# usb2cmi.net
KiCad netlist of a schematic drawn in EAGLE
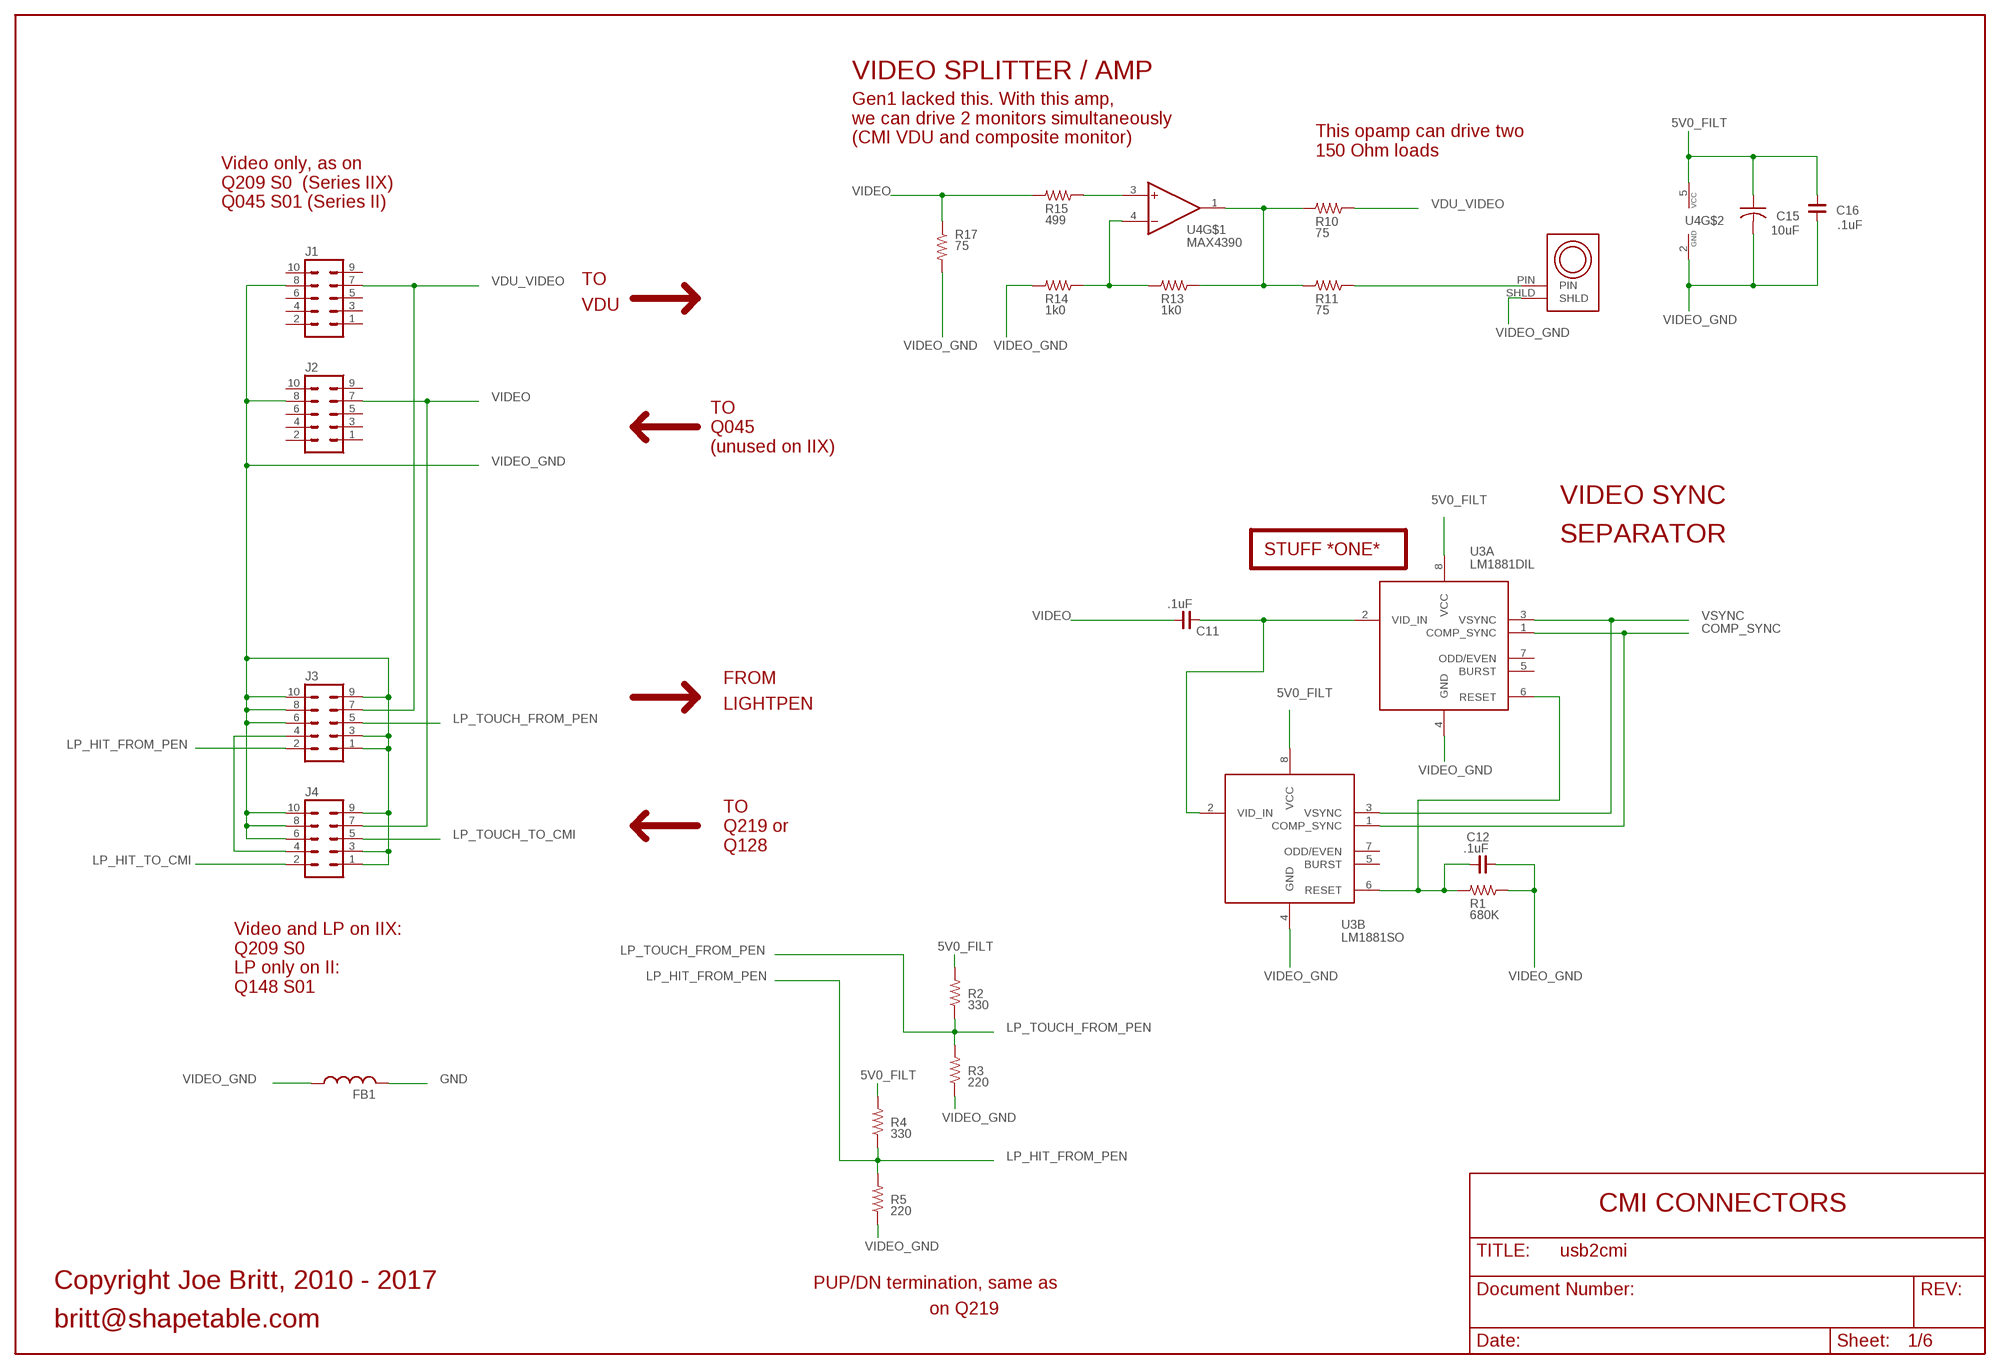
[diagram p0: schematic, sheet 1]
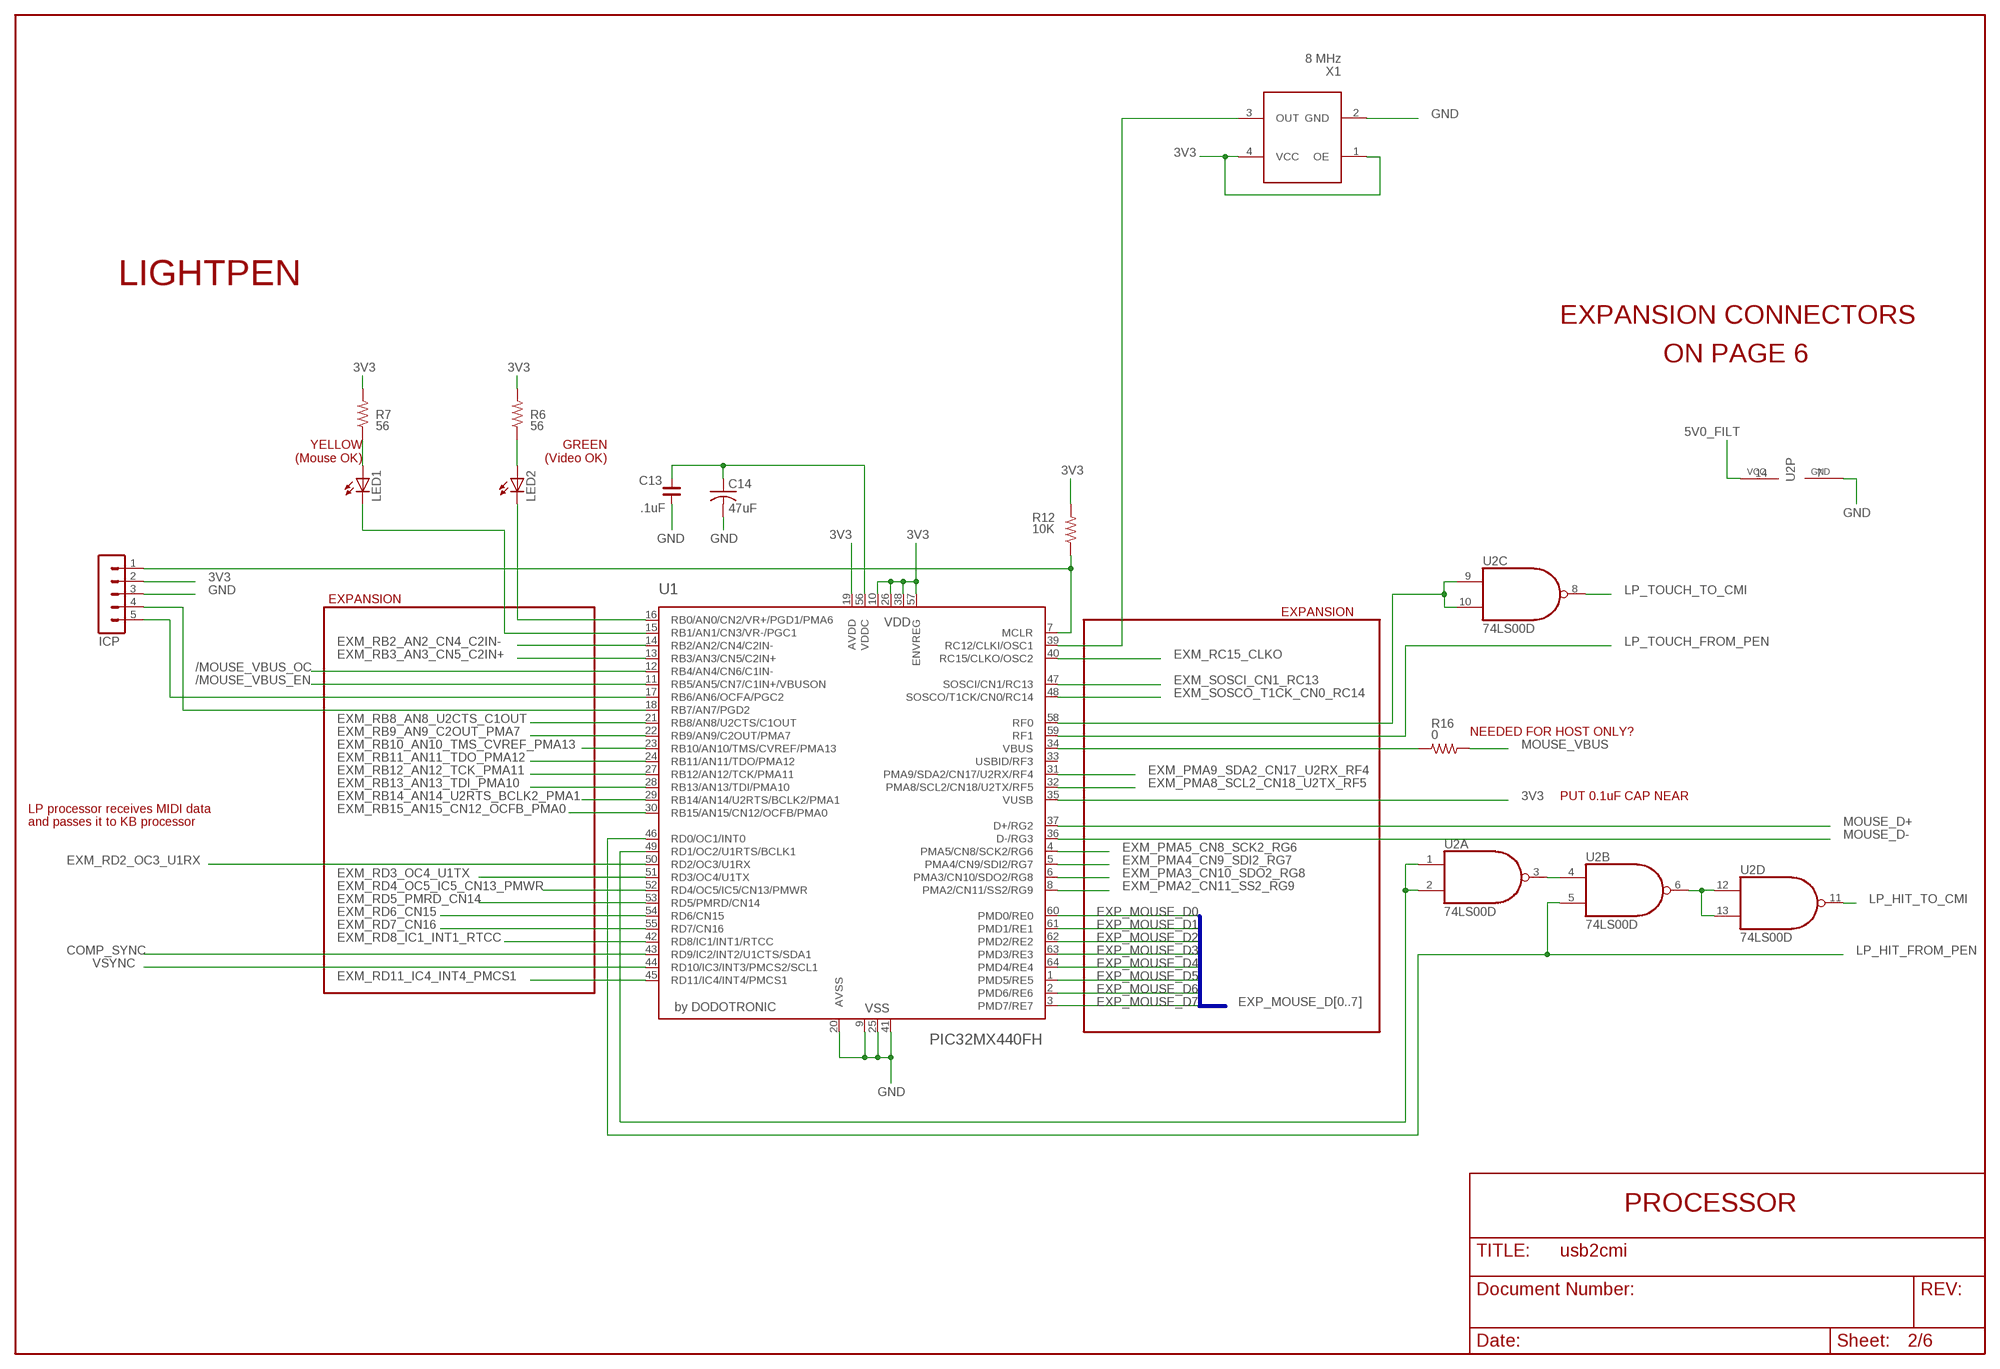
[diagram p1: schematic, sheet 2]
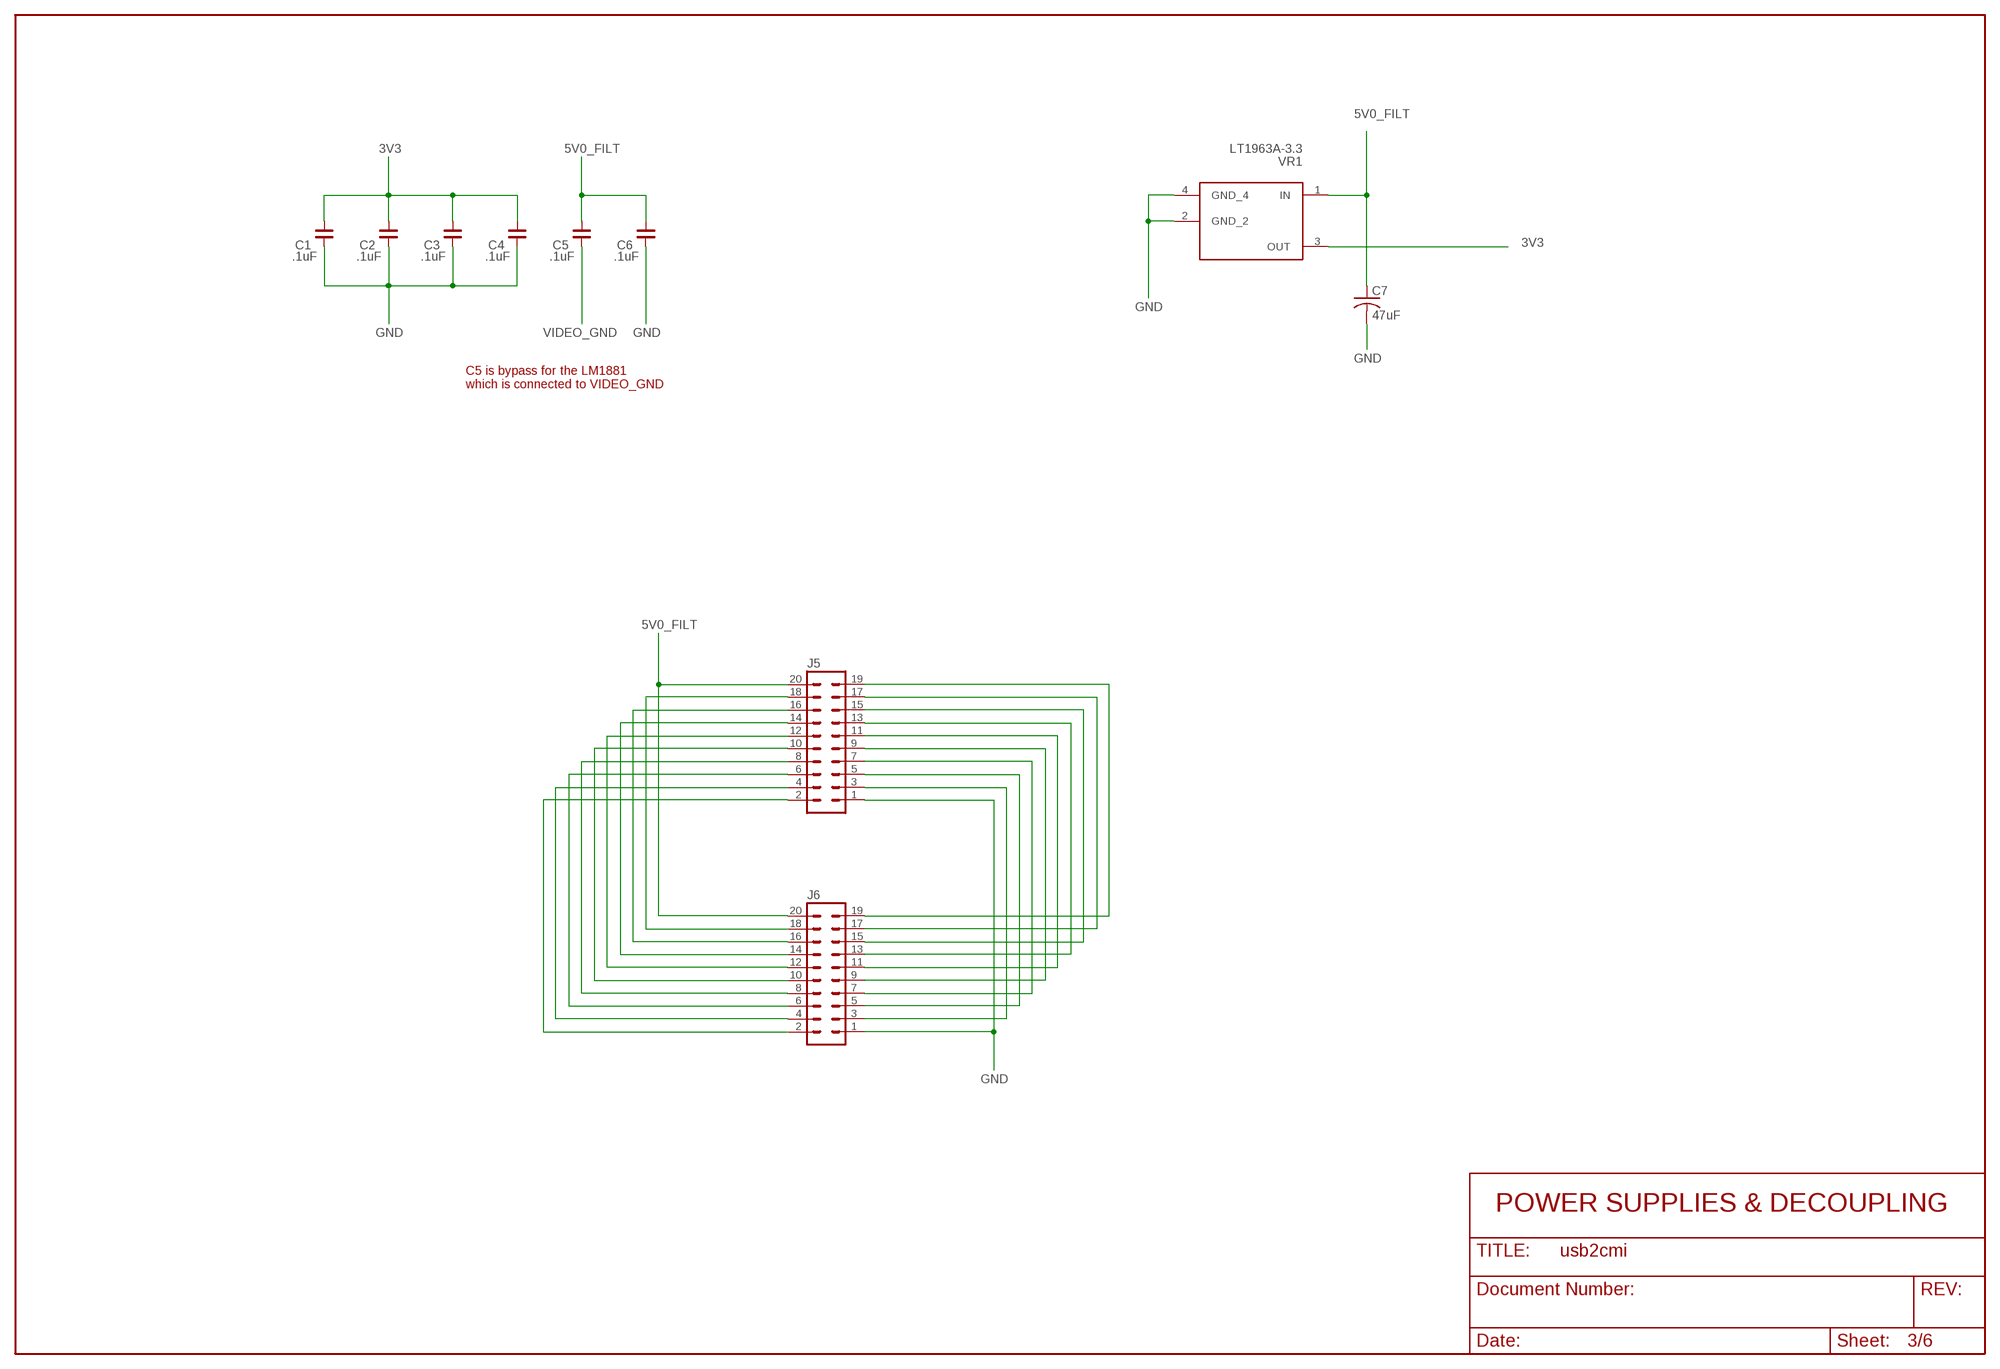
[diagram p2: schematic, sheet 3]
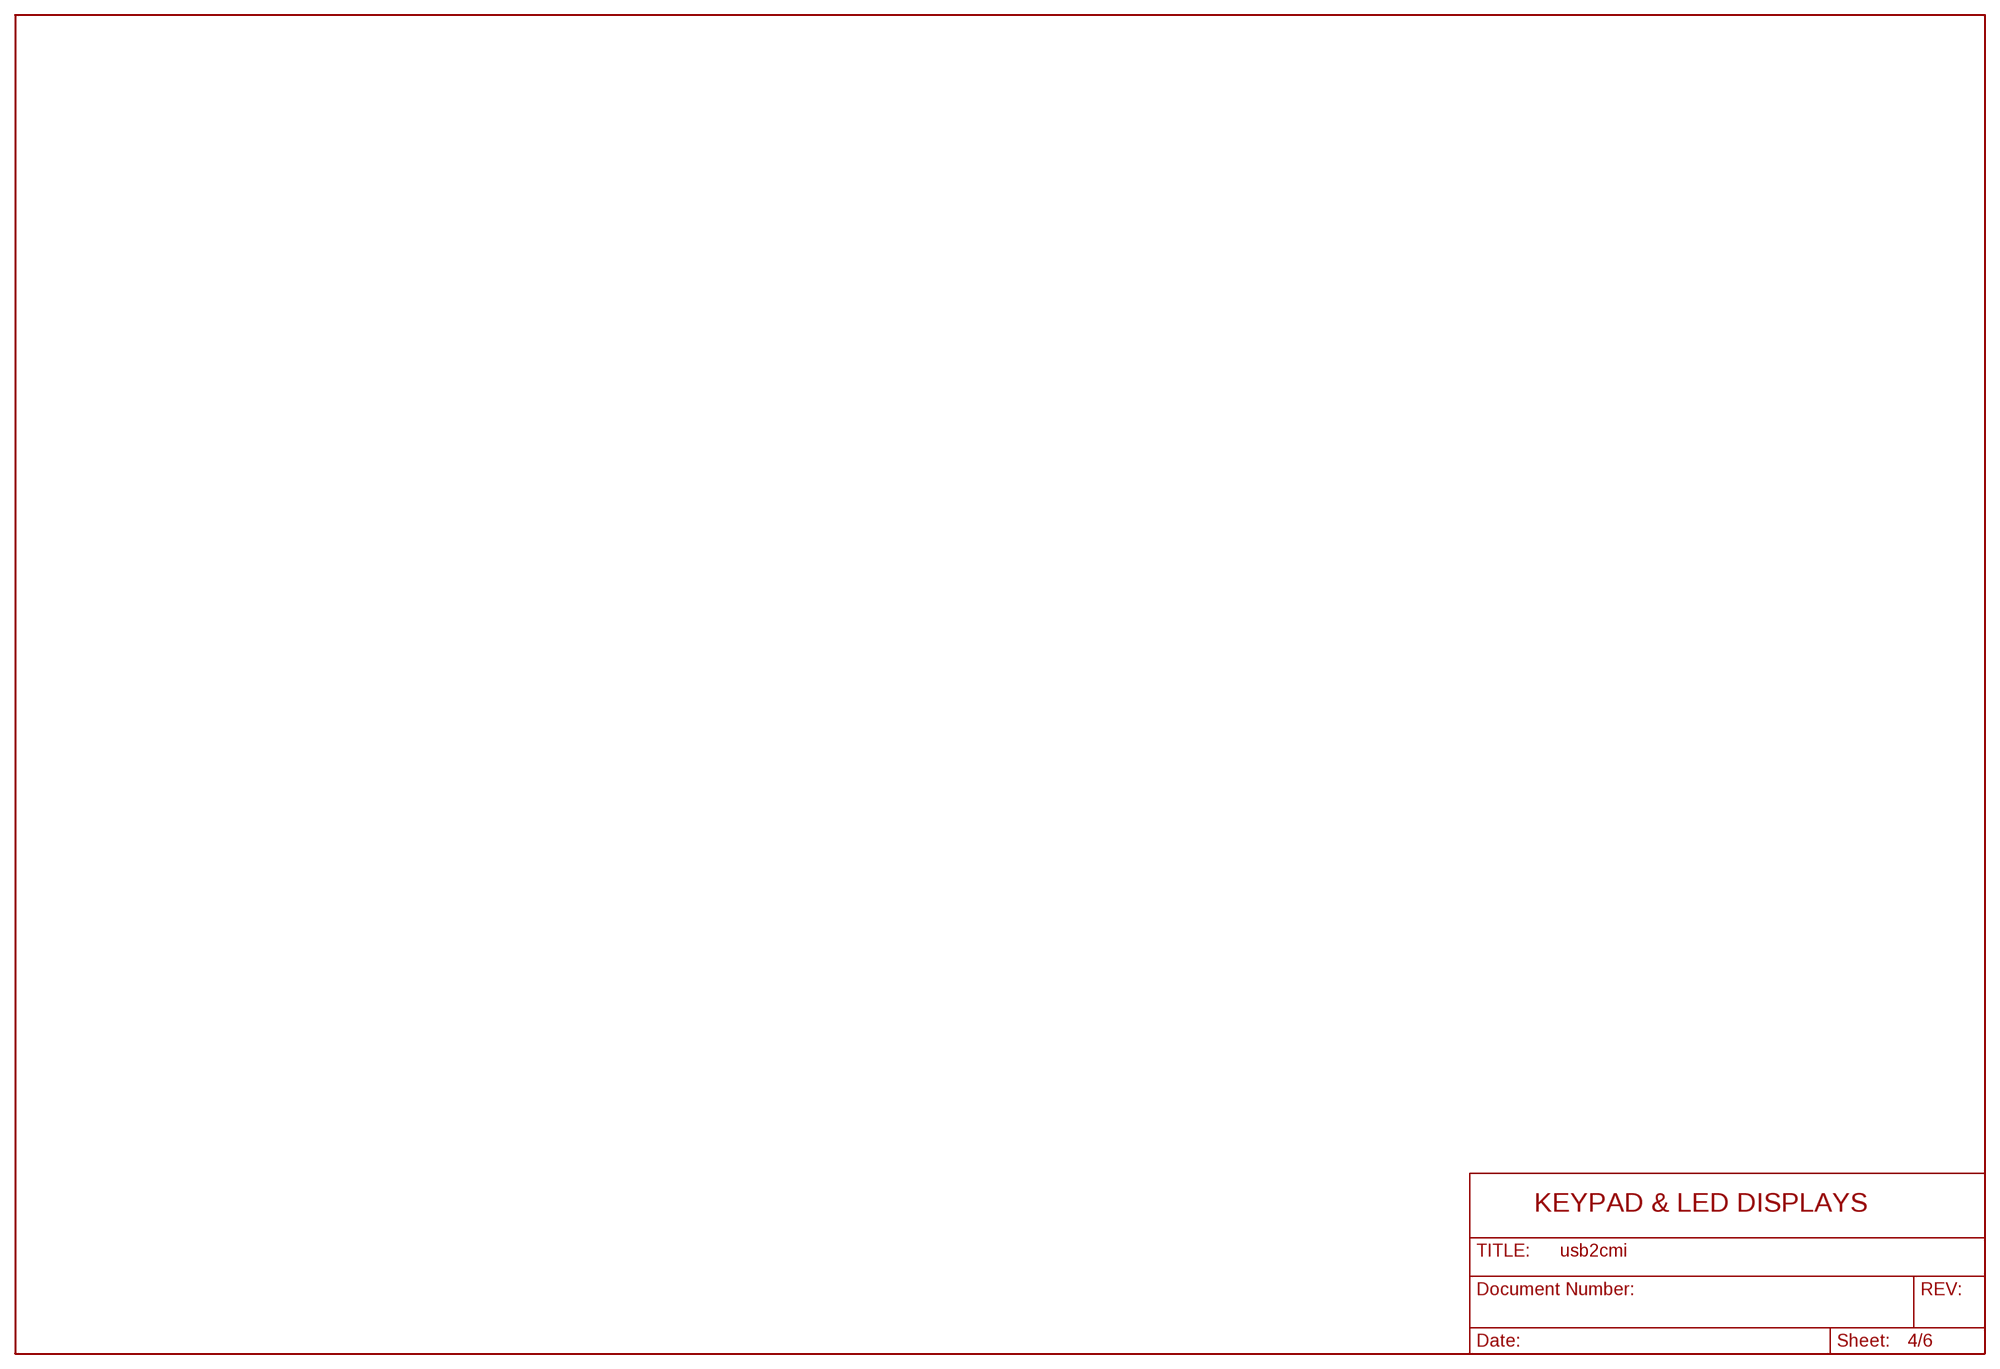
[diagram p3: schematic, sheet 4]
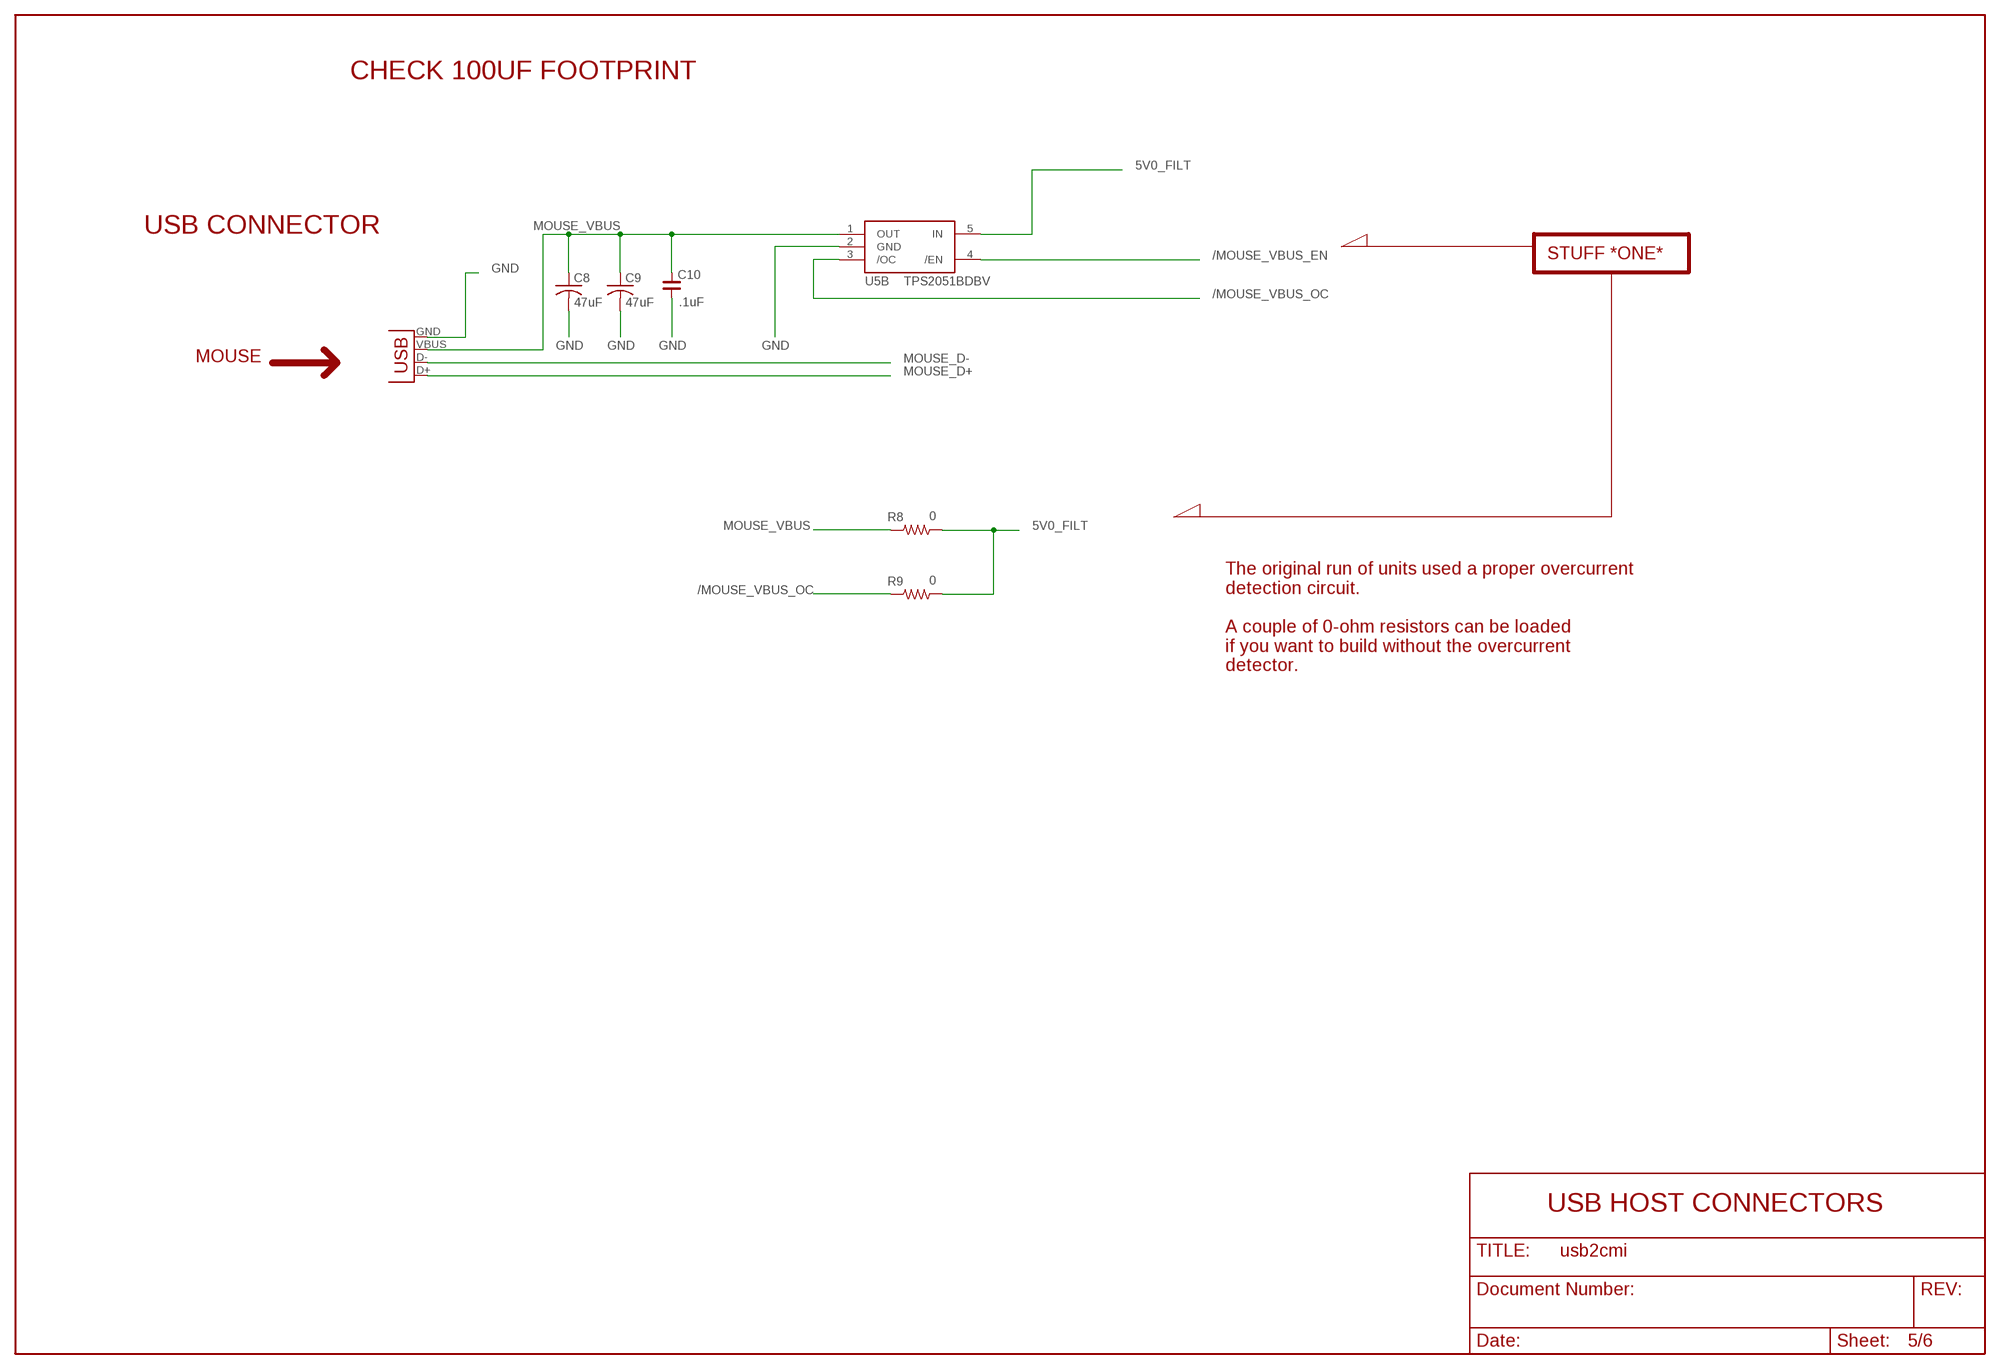
[diagram p4: schematic, sheet 5]
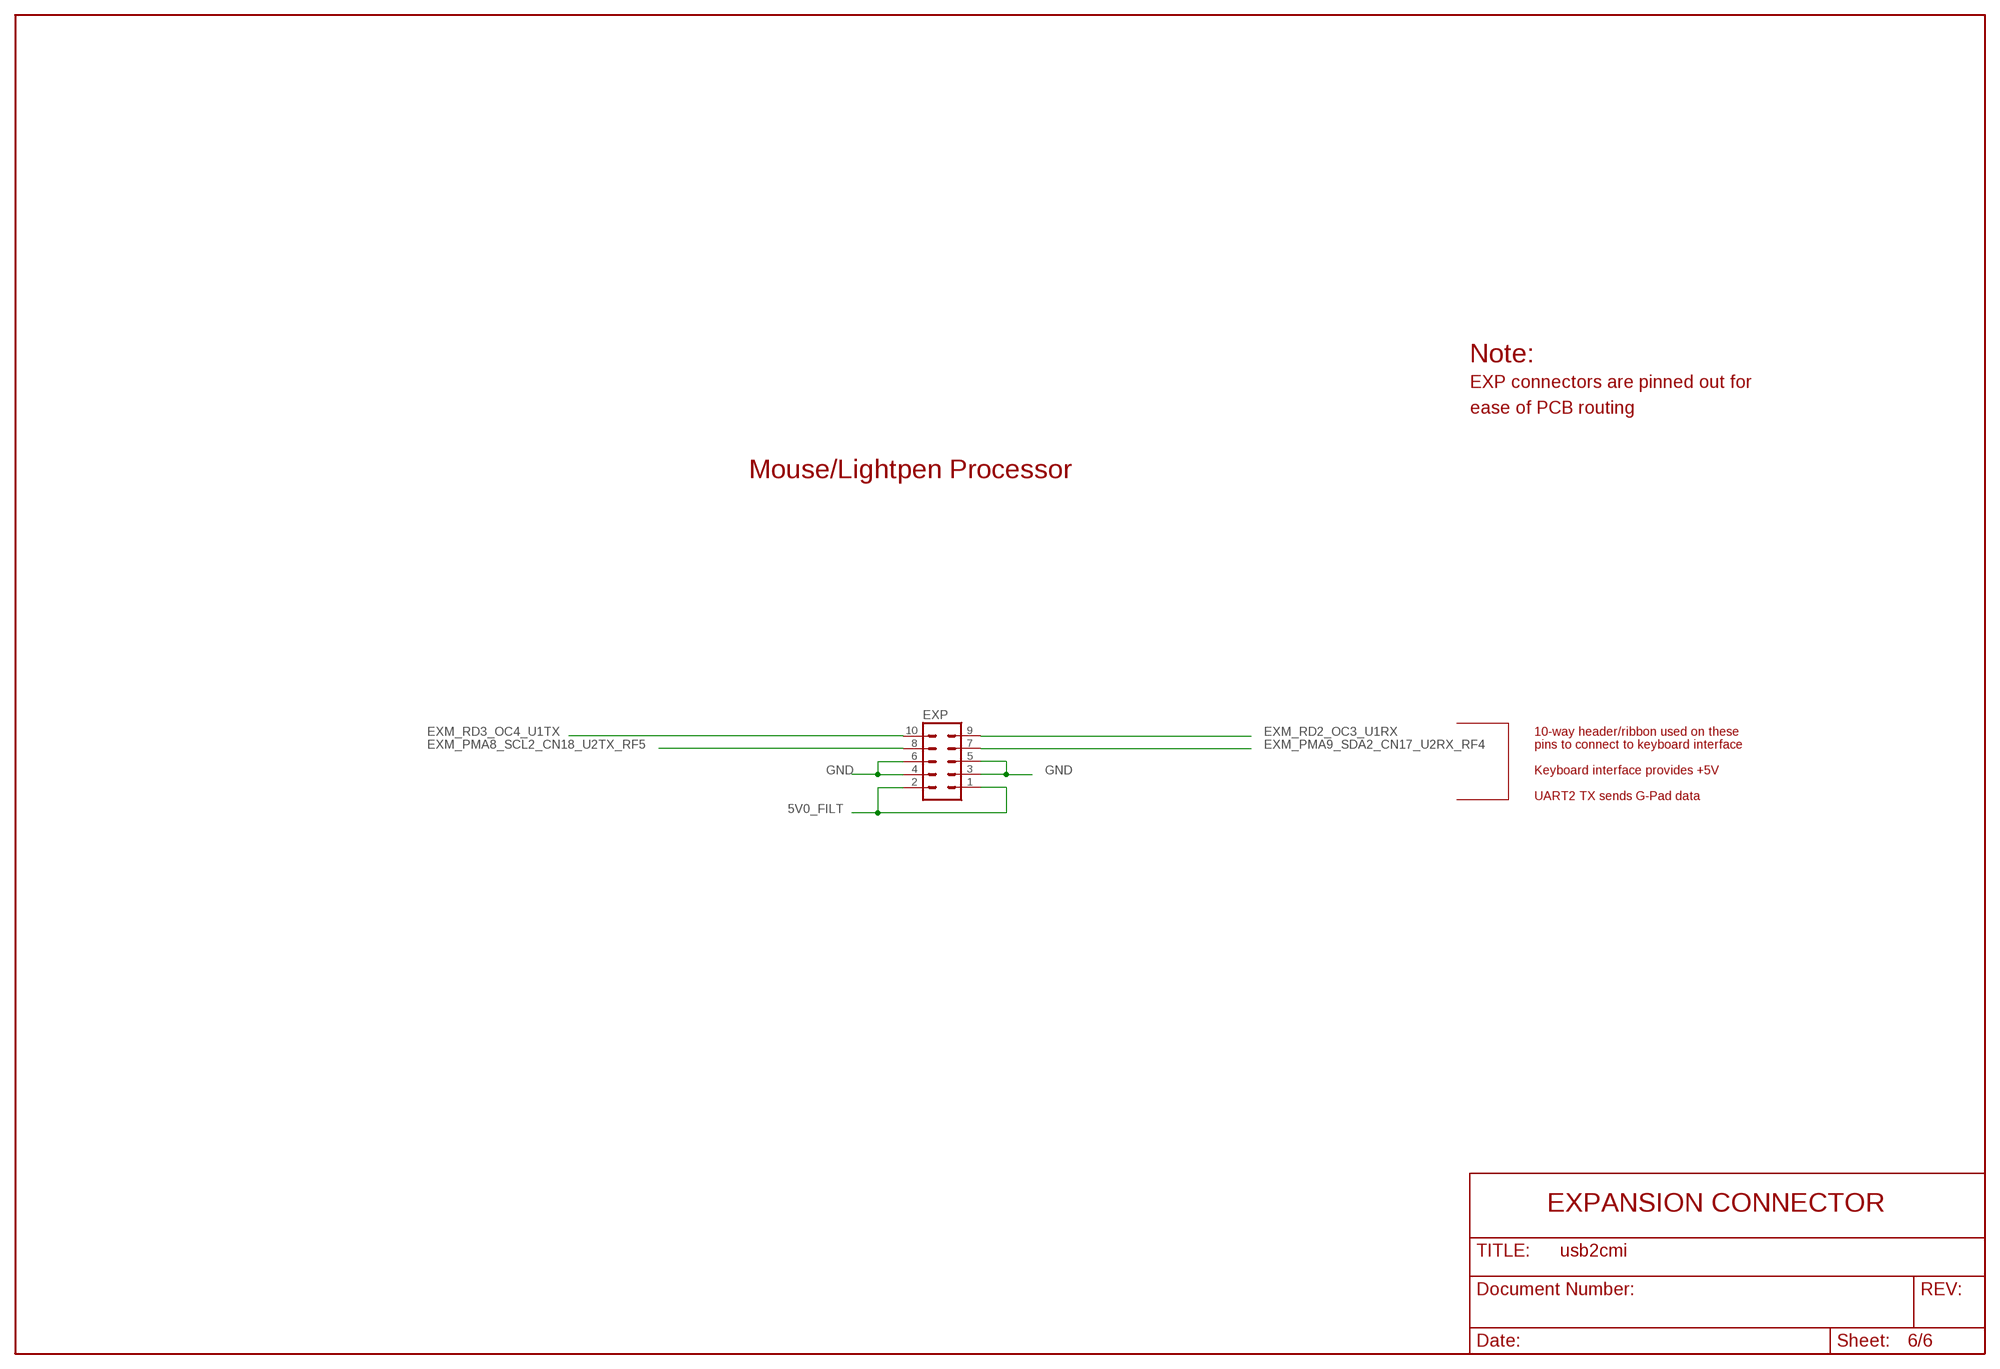
[diagram p5: schematic, sheet 6]

(export (version "E")
  (design (tool "Eeschema 10.0.6"))
  (components
    (comp (ref "C13")
      (value ".1uF")
      (footprint "eagle-import:C0603")
      (libsource (lib "eagle-import") (part "C_0603"))
    )
    (comp (ref "C14")
      (value "47uF")
      (footprint "eagle-import:C0805")
      (libsource (lib "eagle-import") (part "C-USC0805"))
    )
    (comp (ref "ICP")
      (value "MA05-1")
      (footprint "eagle-import:MA05-1")
      (libsource (lib "eagle-import") (part "MA05-1"))
    )
    (comp (ref "LED1")
      (value "LEDCHIPLED_0805")
      (footprint "eagle-import:CHIPLED_0805")
      (libsource (lib "eagle-import") (part "LEDCHIPLED_0805"))
    )
    (comp (ref "LED2")
      (value "LEDCHIPLED_0805")
      (footprint "eagle-import:CHIPLED_0805")
      (libsource (lib "eagle-import") (part "LEDCHIPLED_0805"))
    )
    (comp (ref "R6")
      (value "56")
      (footprint "eagle-import:R0603")
      (libsource (lib "eagle-import") (part "R_0603"))
    )
    (comp (ref "R7")
      (value "56")
      (footprint "eagle-import:R0603")
      (libsource (lib "eagle-import") (part "R_0603"))
    )
    (comp (ref "R12")
      (value "10K")
      (footprint "eagle-import:R0603")
      (libsource (lib "eagle-import") (part "R_0603"))
    )
    (comp (ref "R16")
      (value "0")
      (footprint "eagle-import:R0603")
      (libsource (lib "eagle-import") (part "R_0603"))
    )
    (comp (ref "U1")
      (value "PIC32MX440FH")
      (footprint "eagle-import:TQFP64-10X10")
      (libsource (lib "eagle-import") (part "PIC32MX440FH"))
    )
    (comp (ref "U2")
      (value "74LS00D")
      (footprint "eagle-import:SO14")
      (libsource (lib "eagle-import") (part "7400DLS"))
    )
    (comp (ref "X1")
      (value "8 MHz")
      (footprint "eagle-import:CTS-OSC")
      (libsource (lib "eagle-import") (part "CTS-OSC"))
    )
    (comp (ref "EXP")
      (value "MA05-2")
      (footprint "eagle-import:MA05-2")
      (libsource (lib "eagle-import") (part "MA05-2"))
    )
    (comp (ref "C11")
      (value ".1uF")
      (footprint "eagle-import:C0603")
      (libsource (lib "eagle-import") (part "C_0603"))
    )
    (comp (ref "C12")
      (value ".1uF")
      (footprint "eagle-import:C0603")
      (libsource (lib "eagle-import") (part "C_0603"))
    )
    (comp (ref "C15")
      (value "10uF")
      (footprint "eagle-import:C0805")
      (libsource (lib "eagle-import") (part "C-USC0805"))
    )
    (comp (ref "C16")
      (value ".1uF")
      (footprint "eagle-import:C0603")
      (libsource (lib "eagle-import") (part "C_0603"))
    )
    (comp (ref "FB1")
      (value "L-US0207/15")
      (footprint "eagle-import:0207_15")
      (libsource (lib "eagle-import") (part "L-US0207/15"))
    )
    (comp (ref "J1")
      (value "10H")
      (footprint "eagle-import:10H")
      (libsource (lib "eagle-import") (part "10H"))
    )
    (comp (ref "J2")
      (value "ML10")
      (footprint "eagle-import:ML10")
      (libsource (lib "eagle-import") (part "ML10"))
    )
    (comp (ref "J3")
      (value "10H")
      (footprint "eagle-import:10H")
      (libsource (lib "eagle-import") (part "10H"))
    )
    (comp (ref "J4")
      (value "ML10")
      (footprint "eagle-import:ML10")
      (libsource (lib "eagle-import") (part "ML10"))
    )
    (comp (ref "J8")
      (value "CUI RCJ-044")
      (footprint "eagle-import:RCA-SHIELDED")
      (libsource (lib "eagle-import") (part "RCA-HSC"))
    )
    (comp (ref "R1")
      (value "680K")
      (footprint "eagle-import:R0603")
      (libsource (lib "eagle-import") (part "R_0603"))
    )
    (comp (ref "R2")
      (value "330")
      (footprint "eagle-import:R0603")
      (libsource (lib "eagle-import") (part "R_0603"))
    )
    (comp (ref "R3")
      (value "220")
      (footprint "eagle-import:R0603")
      (libsource (lib "eagle-import") (part "R_0603"))
    )
    (comp (ref "R4")
      (value "330")
      (footprint "eagle-import:R0603")
      (libsource (lib "eagle-import") (part "R_0603"))
    )
    (comp (ref "R5")
      (value "220")
      (footprint "eagle-import:R0603")
      (libsource (lib "eagle-import") (part "R_0603"))
    )
    (comp (ref "R10")
      (value "75")
      (footprint "eagle-import:R0603")
      (libsource (lib "eagle-import") (part "R_0603"))
    )
    (comp (ref "R11")
      (value "75")
      (footprint "eagle-import:R0603")
      (libsource (lib "eagle-import") (part "R_0603"))
    )
    (comp (ref "R13")
      (value "1k0")
      (footprint "eagle-import:R0603")
      (libsource (lib "eagle-import") (part "R_0603"))
    )
    (comp (ref "R14")
      (value "1k0")
      (footprint "eagle-import:R0603")
      (libsource (lib "eagle-import") (part "R_0603"))
    )
    (comp (ref "R15")
      (value "499")
      (footprint "eagle-import:R0603")
      (libsource (lib "eagle-import") (part "R_0603"))
    )
    (comp (ref "R17")
      (value "75")
      (footprint "eagle-import:R0603")
      (libsource (lib "eagle-import") (part "R_0603"))
    )
    (comp (ref "U3A")
      (value "LM1881DIL")
      (footprint "eagle-import:DIL08")
      (libsource (lib "eagle-import") (part "LM1881DIL"))
    )
    (comp (ref "U3B")
      (value "LM1881SO")
      (footprint "eagle-import:SO08")
      (libsource (lib "eagle-import") (part "LM1881SO"))
    )
    (comp (ref "U4")
      (value "MAX4390")
      (footprint "eagle-import:SOT23-5L")
      (libsource (lib "eagle-import") (part "MAX4390"))
    )
    (comp (ref "C8")
      (value "47uF")
      (footprint "eagle-import:C0805")
      (libsource (lib "eagle-import") (part "C-USC0805"))
    )
    (comp (ref "C9")
      (value "47uF")
      (footprint "eagle-import:C0805")
      (libsource (lib "eagle-import") (part "C-USC0805"))
    )
    (comp (ref "C10")
      (value ".1uF")
      (footprint "eagle-import:C0603")
      (libsource (lib "eagle-import") (part "C_0603"))
    )
    (comp (ref "J7")
      (value "USB-A-H")
      (footprint "eagle-import:USB-A-H")
      (libsource (lib "eagle-import") (part "USB-A-H"))
    )
    (comp (ref "R8")
      (value "0")
      (footprint "eagle-import:R0603")
      (libsource (lib "eagle-import") (part "R_0603"))
    )
    (comp (ref "R9")
      (value "0")
      (footprint "eagle-import:R0603")
      (libsource (lib "eagle-import") (part "R_0603"))
    )
    (comp (ref "U5B")
      (value "TPS2051BDBV")
      (footprint "eagle-import:DBV-5")
      (libsource (lib "eagle-import") (part "TPS2041BDBV"))
    )
    (comp (ref "C1")
      (value ".1uF")
      (footprint "eagle-import:C0603")
      (libsource (lib "eagle-import") (part "C_0603"))
    )
    (comp (ref "C2")
      (value ".1uF")
      (footprint "eagle-import:C0603")
      (libsource (lib "eagle-import") (part "C_0603"))
    )
    (comp (ref "C3")
      (value ".1uF")
      (footprint "eagle-import:C0603")
      (libsource (lib "eagle-import") (part "C_0603"))
    )
    (comp (ref "C4")
      (value ".1uF")
      (footprint "eagle-import:C0603")
      (libsource (lib "eagle-import") (part "C_0603"))
    )
    (comp (ref "C5")
      (value ".1uF")
      (footprint "eagle-import:C0603")
      (libsource (lib "eagle-import") (part "C_0603"))
    )
    (comp (ref "C6")
      (value ".1uF")
      (footprint "eagle-import:C0603")
      (libsource (lib "eagle-import") (part "C_0603"))
    )
    (comp (ref "C7")
      (value "47uF")
      (footprint "eagle-import:C0805")
      (libsource (lib "eagle-import") (part "C-USC0805"))
    )
    (comp (ref "J5")
      (value "20H")
      (footprint "eagle-import:20H")
      (libsource (lib "eagle-import") (part "20H"))
    )
    (comp (ref "J6")
      (value "ML20")
      (footprint "eagle-import:ML20")
      (libsource (lib "eagle-import") (part "ML20"))
    )
    (comp (ref "VR1")
      (value "LT1963A-3.3")
      (footprint "eagle-import:SOT-223")
      (libsource (lib "eagle-import") (part "LINEAR-REG-SOT223"))
    )
  )
  (nets
    (net (code "2") (name "3V3") (class "Default")
      (node (ref "C1") (pin "1") (pinfunction "1_1") (pintype "passive"))
      (node (ref "C2") (pin "1") (pinfunction "1_1") (pintype "passive"))
      (node (ref "C3") (pin "1") (pinfunction "1_1") (pintype "passive"))
      (node (ref "C4") (pin "1") (pinfunction "1_1") (pintype "passive"))
      (node (ref "ICP") (pin "2") (pinfunction "2_2") (pintype "passive"))
      (node (ref "R12") (pin "2") (pinfunction "2_2") (pintype "passive"))
      (node (ref "R6") (pin "2") (pinfunction "2_2") (pintype "passive"))
      (node (ref "R7") (pin "2") (pinfunction "2_2") (pintype "passive"))
      (node (ref "U1") (pin "10") (pinfunction "VDD_10") (pintype "power_in"))
      (node (ref "U1") (pin "19") (pinfunction "AVDD_19") (pintype "bidirectional"))
      (node (ref "U1") (pin "26") (pinfunction "VDD_26") (pintype "power_in"))
      (node (ref "U1") (pin "35") (pinfunction "VUSB_35") (pintype "bidirectional"))
      (node (ref "U1") (pin "38") (pinfunction "VDD_38") (pintype "power_in"))
      (node (ref "U1") (pin "57") (pinfunction "ENVREG_57") (pintype "bidirectional"))
      (node (ref "VR1") (pin "3") (pinfunction "OUT_3") (pintype "bidirectional"))
      (node (ref "X1") (pin "1") (pinfunction "OE_1") (pintype "input"))
      (node (ref "X1") (pin "4") (pinfunction "VCC_4") (pintype "power_in"))
    )
    (net (code "3") (name "5V0_FILT") (class "Default")
      (node (ref "C15") (pin "1") (pinfunction "1_1") (pintype "passive"))
      (node (ref "C16") (pin "2") (pinfunction "2_2") (pintype "passive"))
      (node (ref "C5") (pin "1") (pinfunction "1_1") (pintype "passive"))
      (node (ref "C6") (pin "1") (pinfunction "1_1") (pintype "passive"))
      (node (ref "C7") (pin "1") (pinfunction "1_1") (pintype "passive"))
      (node (ref "EXP") (pin "1") (pinfunction "1_1") (pintype "passive"))
      (node (ref "EXP") (pin "2") (pinfunction "2_2") (pintype "passive"))
      (node (ref "J5") (pin "20") (pinfunction "20_20") (pintype "passive"))
      (node (ref "J6") (pin "20") (pinfunction "20_20") (pintype "passive"))
      (node (ref "R2") (pin "2") (pinfunction "2_2") (pintype "passive"))
      (node (ref "R4") (pin "2") (pinfunction "2_2") (pintype "passive"))
      (node (ref "R8") (pin "1") (pinfunction "1_1") (pintype "passive"))
      (node (ref "R9") (pin "1") (pinfunction "1_1") (pintype "passive"))
      (node (ref "U2") (pin "14") (pinfunction "VCC_14") (pintype "power_in"))
      (node (ref "U3A") (pin "8") (pinfunction "VCC_8") (pintype "power_in"))
      (node (ref "U3B") (pin "8") (pinfunction "VCC_8") (pintype "power_in"))
      (node (ref "U4") (pin "5") (pinfunction "VCC_5") (pintype "power_in"))
      (node (ref "U5B") (pin "5") (pinfunction "IN_5") (pintype "input"))
      (node (ref "VR1") (pin "1") (pinfunction "IN_1") (pintype "bidirectional"))
    )
    (net (code "4") (name "COMP_SYNC") (class "Default")
      (node (ref "U1") (pin "43") (pinfunction "RD9/IC2/INT2/U1CTS/SDA1_43") (pintype "bidirectional"))
      (node (ref "U3A") (pin "1") (pinfunction "COMP_SYNC_1") (pintype "output"))
      (node (ref "U3B") (pin "1") (pinfunction "COMP_SYNC_1") (pintype "output"))
    )
    (net (code "5") (name "EXM_PMA2_CN11_SS2_RG9") (class "Default")
      (node (ref "U1") (pin "8") (pinfunction "PMA2/CN11/SS2/RG9_8") (pintype "bidirectional"))
    )
    (net (code "6") (name "EXM_PMA3_CN10_SDO2_RG8") (class "Default")
      (node (ref "U1") (pin "6") (pinfunction "PMA3/CN10/SDO2/RG8_6") (pintype "bidirectional"))
    )
    (net (code "7") (name "EXM_PMA4_CN9_SDI2_RG7") (class "Default")
      (node (ref "U1") (pin "5") (pinfunction "PMA4/CN9/SDI2/RG7_5") (pintype "bidirectional"))
    )
    (net (code "8") (name "EXM_PMA5_CN8_SCK2_RG6") (class "Default")
      (node (ref "U1") (pin "4") (pinfunction "PMA5/CN8/SCK2/RG6_4") (pintype "bidirectional"))
    )
    (net (code "9") (name "EXM_PMA8_SCL2_CN18_U2TX_RF5") (class "Default")
      (node (ref "EXP") (pin "8") (pinfunction "8_8") (pintype "passive"))
      (node (ref "U1") (pin "32") (pinfunction "PMA8/SCL2/CN18/U2TX/RF5_32") (pintype "bidirectional"))
    )
    (net (code "10") (name "EXM_PMA9_SDA2_CN17_U2RX_RF4") (class "Default")
      (node (ref "EXP") (pin "7") (pinfunction "7_7") (pintype "passive"))
      (node (ref "U1") (pin "31") (pinfunction "PMA9/SDA2/CN17/U2RX/RF4_31") (pintype "bidirectional"))
    )
    (net (code "11") (name "EXM_RB2_AN2_CN4_C2IN-") (class "Default")
      (node (ref "U1") (pin "14") (pinfunction "RB2/AN2/CN4/C2IN-_14") (pintype "bidirectional"))
    )
    (net (code "12") (name "EXM_RB3_AN3_CN5_C2IN+") (class "Default")
      (node (ref "U1") (pin "13") (pinfunction "RB3/AN3/CN5/C2IN+_13") (pintype "bidirectional"))
    )
    (net (code "13") (name "EXM_RB8_AN8_U2CTS_C1OUT") (class "Default")
      (node (ref "U1") (pin "21") (pinfunction "RB8/AN8/U2CTS/C1OUT_21") (pintype "bidirectional"))
    )
    (net (code "14") (name "EXM_RB9_AN9_C2OUT_PMA7") (class "Default")
      (node (ref "U1") (pin "22") (pinfunction "RB9/AN9/C2OUT/PMA7_22") (pintype "bidirectional"))
    )
    (net (code "15") (name "EXM_RB10_AN10_TMS_CVREF_PMA13") (class "Default")
      (node (ref "U1") (pin "23") (pinfunction "RB10/AN10/TMS/CVREF/PMA13_23") (pintype "bidirectional"))
    )
    (net (code "16") (name "EXM_RB11_AN11_TDO_PMA12") (class "Default")
      (node (ref "U1") (pin "24") (pinfunction "RB11/AN11/TDO/PMA12_24") (pintype "bidirectional"))
    )
    (net (code "17") (name "EXM_RB12_AN12_TCK_PMA11") (class "Default")
      (node (ref "U1") (pin "27") (pinfunction "RB12/AN12/TCK/PMA11_27") (pintype "bidirectional"))
    )
    (net (code "18") (name "EXM_RB13_AN13_TDI_PMA10") (class "Default")
      (node (ref "U1") (pin "28") (pinfunction "RB13/AN13/TDI/PMA10_28") (pintype "bidirectional"))
    )
    (net (code "19") (name "EXM_RB14_AN14_U2RTS_BCLK2_PMA1") (class "Default")
      (node (ref "U1") (pin "29") (pinfunction "RB14/AN14/U2RTS/BCLK2/PMA1_29") (pintype "bidirectional"))
    )
    (net (code "20") (name "EXM_RB15_AN15_CN12_OCFB_PMA0") (class "Default")
      (node (ref "U1") (pin "30") (pinfunction "RB15/AN15/CN12/OCFB/PMA0_30") (pintype "bidirectional"))
    )
    (net (code "21") (name "EXM_RC15_CLKO") (class "Default")
      (node (ref "U1") (pin "40") (pinfunction "RC15/CLKO/OSC2_40") (pintype "bidirectional"))
    )
    (net (code "22") (name "EXM_RD2_OC3_U1RX") (class "Default")
      (node (ref "EXP") (pin "9") (pinfunction "9_9") (pintype "passive"))
      (node (ref "U1") (pin "50") (pinfunction "RD2/OC3/U1RX_50") (pintype "bidirectional"))
    )
    (net (code "23") (name "EXM_RD3_OC4_U1TX") (class "Default")
      (node (ref "EXP") (pin "10") (pinfunction "10_10") (pintype "passive"))
      (node (ref "U1") (pin "51") (pinfunction "RD3/OC4/U1TX_51") (pintype "bidirectional"))
    )
    (net (code "24") (name "EXM_RD4_OC5_IC5_CN13_PMWR") (class "Default")
      (node (ref "U1") (pin "52") (pinfunction "RD4/OC5/IC5/CN13/PMWR_52") (pintype "bidirectional"))
    )
    (net (code "25") (name "EXM_RD5_PMRD_CN14") (class "Default")
      (node (ref "U1") (pin "53") (pinfunction "RD5/PMRD/CN14_53") (pintype "bidirectional"))
    )
    (net (code "26") (name "EXM_RD6_CN15") (class "Default")
      (node (ref "U1") (pin "54") (pinfunction "RD6/CN15_54") (pintype "bidirectional"))
    )
    (net (code "27") (name "EXM_RD7_CN16") (class "Default")
      (node (ref "U1") (pin "55") (pinfunction "RD7/CN16_55") (pintype "bidirectional"))
    )
    (net (code "28") (name "EXM_RD8_IC1_INT1_RTCC") (class "Default")
      (node (ref "U1") (pin "42") (pinfunction "RD8/IC1/INT1/RTCC_42") (pintype "bidirectional"))
    )
    (net (code "29") (name "EXM_RD11_IC4_INT4_PMCS1") (class "Default")
      (node (ref "U1") (pin "45") (pinfunction "RD11/IC4/INT4/PMCS1_45") (pintype "bidirectional"))
    )
    (net (code "30") (name "EXM_SOSCI_CN1_RC13") (class "Default")
      (node (ref "U1") (pin "47") (pinfunction "SOSCI/CN1/RC13_47") (pintype "bidirectional"))
    )
    (net (code "31") (name "EXM_SOSCO_T1CK_CN0_RC14") (class "Default")
      (node (ref "U1") (pin "48") (pinfunction "SOSCO/T1CK/CN0/RC14_48") (pintype "bidirectional"))
    )
    (net (code "32") (name "EXP_MOUSE_D0") (class "Default")
      (node (ref "U1") (pin "60") (pinfunction "PMD0/RE0_60") (pintype "bidirectional"))
    )
    (net (code "33") (name "EXP_MOUSE_D1") (class "Default")
      (node (ref "U1") (pin "61") (pinfunction "PMD1/RE1_61") (pintype "bidirectional"))
    )
    (net (code "34") (name "EXP_MOUSE_D2") (class "Default")
      (node (ref "U1") (pin "62") (pinfunction "PMD2/RE2_62") (pintype "bidirectional"))
    )
    (net (code "35") (name "EXP_MOUSE_D3") (class "Default")
      (node (ref "U1") (pin "63") (pinfunction "PMD3/RE3_63") (pintype "bidirectional"))
    )
    (net (code "36") (name "EXP_MOUSE_D4") (class "Default")
      (node (ref "U1") (pin "64") (pinfunction "PMD4/RE4_64") (pintype "bidirectional"))
    )
    (net (code "37") (name "EXP_MOUSE_D5") (class "Default")
      (node (ref "U1") (pin "1") (pinfunction "PMD5/RE5_1") (pintype "bidirectional"))
    )
    (net (code "38") (name "EXP_MOUSE_D6") (class "Default")
      (node (ref "U1") (pin "2") (pinfunction "PMD6/RE6_2") (pintype "bidirectional"))
    )
    (net (code "39") (name "EXP_MOUSE_D7") (class "Default")
      (node (ref "U1") (pin "3") (pinfunction "PMD7/RE7_3") (pintype "bidirectional"))
    )
    (net (code "40") (name "GND") (class "Default")
      (node (ref "C1") (pin "2") (pinfunction "2_2") (pintype "passive"))
      (node (ref "C10") (pin "2") (pinfunction "2_2") (pintype "passive"))
      (node (ref "C13") (pin "2") (pinfunction "2_2") (pintype "passive"))
      (node (ref "C14") (pin "2") (pinfunction "2_2") (pintype "passive"))
      (node (ref "C2") (pin "2") (pinfunction "2_2") (pintype "passive"))
      (node (ref "C3") (pin "2") (pinfunction "2_2") (pintype "passive"))
      (node (ref "C4") (pin "2") (pinfunction "2_2") (pintype "passive"))
      (node (ref "C6") (pin "2") (pinfunction "2_2") (pintype "passive"))
      (node (ref "C7") (pin "2") (pinfunction "2_2") (pintype "passive"))
      (node (ref "C8") (pin "2") (pinfunction "2_2") (pintype "passive"))
      (node (ref "C9") (pin "2") (pinfunction "2_2") (pintype "passive"))
      (node (ref "EXP") (pin "3") (pinfunction "3_3") (pintype "passive"))
      (node (ref "EXP") (pin "4") (pinfunction "4_4") (pintype "passive"))
      (node (ref "EXP") (pin "5") (pinfunction "5_5") (pintype "passive"))
      (node (ref "EXP") (pin "6") (pinfunction "6_6") (pintype "passive"))
      (node (ref "FB1") (pin "2") (pinfunction "2_2") (pintype "passive"))
      (node (ref "ICP") (pin "3") (pinfunction "3_3") (pintype "passive"))
      (node (ref "J5") (pin "1") (pinfunction "1_1") (pintype "passive"))
      (node (ref "J6") (pin "1") (pinfunction "1_1") (pintype "passive"))
      (node (ref "J7") (pin "GND") (pinfunction "GND_GND") (pintype "bidirectional"))
      (node (ref "U1") (pin "20") (pinfunction "AVSS_20") (pintype "bidirectional"))
      (node (ref "U1") (pin "25") (pinfunction "VSS_25") (pintype "power_in"))
      (node (ref "U1") (pin "41") (pinfunction "VSS_41") (pintype "power_in"))
      (node (ref "U1") (pin "9") (pinfunction "VSS_9") (pintype "power_in"))
      (node (ref "U2") (pin "7") (pinfunction "GND_7") (pintype "power_in"))
      (node (ref "U5B") (pin "2") (pinfunction "GND_2") (pintype "power_in"))
      (node (ref "VR1") (pin "2") (pinfunction "GND_2_2") (pintype "bidirectional"))
      (node (ref "VR1") (pin "4") (pinfunction "GND_4_4") (pintype "bidirectional"))
      (node (ref "X1") (pin "2") (pinfunction "GND_2") (pintype "power_in"))
    )
    (net (code "41") (name "LP_HIT_FROM_PEN") (class "Default")
      (node (ref "J3") (pin "2") (pinfunction "2_2") (pintype "passive"))
      (node (ref "R4") (pin "1") (pinfunction "1_1") (pintype "passive"))
      (node (ref "R5") (pin "2") (pinfunction "2_2") (pintype "passive"))
      (node (ref "U1") (pin "46") (pinfunction "RD0/OC1/INT0_46") (pintype "bidirectional"))
      (node (ref "U2") (pin "5") (pinfunction "I1_5") (pintype "input"))
    )
    (net (code "42") (name "LP_HIT_TO_CMI") (class "Default")
      (node (ref "J4") (pin "2") (pinfunction "2_2") (pintype "passive"))
      (node (ref "U2") (pin "11") (pinfunction "O_11") (pintype "output"))
    )
    (net (code "43") (name "LP_TOUCH_FROM_PEN") (class "Default")
      (node (ref "J3") (pin "5") (pinfunction "5_5") (pintype "passive"))
      (node (ref "R2") (pin "1") (pinfunction "1_1") (pintype "passive"))
      (node (ref "R3") (pin "2") (pinfunction "2_2") (pintype "passive"))
      (node (ref "U1") (pin "59") (pinfunction "RF1_59") (pintype "bidirectional"))
    )
    (net (code "44") (name "LP_TOUCH_TO_CMI") (class "Default")
      (node (ref "J4") (pin "5") (pinfunction "5_5") (pintype "passive"))
      (node (ref "U2") (pin "8") (pinfunction "O_8") (pintype "output"))
    )
    (net (code "45") (name "MOUSE_D+") (class "Default")
      (node (ref "J7") (pin "D+") (pinfunction "D+_D+") (pintype "bidirectional"))
      (node (ref "U1") (pin "37") (pinfunction "D+/RG2_37") (pintype "bidirectional"))
    )
    (net (code "46") (name "MOUSE_D-") (class "Default")
      (node (ref "J7") (pin "D-") (pinfunction "D-_D-") (pintype "bidirectional"))
      (node (ref "U1") (pin "36") (pinfunction "D-/RG3_36") (pintype "bidirectional"))
    )
    (net (code "47") (name "MOUSE_VBUS") (class "Default")
      (node (ref "C10") (pin "1") (pinfunction "1_1") (pintype "passive"))
      (node (ref "C8") (pin "1") (pinfunction "1_1") (pintype "passive"))
      (node (ref "C9") (pin "1") (pinfunction "1_1") (pintype "passive"))
      (node (ref "J7") (pin "VBUS") (pinfunction "VBUS_VBUS") (pintype "bidirectional"))
      (node (ref "R16") (pin "1") (pinfunction "1_1") (pintype "passive"))
      (node (ref "R8") (pin "2") (pinfunction "2_2") (pintype "passive"))
      (node (ref "U5B") (pin "1") (pinfunction "OUT_1") (pintype "input"))
    )
    (net (code "48") (name "Net-(J3-Pad4)") (class "Default")
      (node (ref "J3") (pin "4") (pinfunction "4_4") (pintype "passive"))
      (node (ref "J4") (pin "4") (pinfunction "4_4") (pintype "passive"))
    )
    (net (code "49") (name "Net-(J5-Pad2)") (class "Default")
      (node (ref "J5") (pin "2") (pinfunction "2_2") (pintype "passive"))
      (node (ref "J6") (pin "2") (pinfunction "2_2") (pintype "passive"))
    )
    (net (code "50") (name "Net-(J5-Pad3)") (class "Default")
      (node (ref "J5") (pin "3") (pinfunction "3_3") (pintype "passive"))
      (node (ref "J6") (pin "3") (pinfunction "3_3") (pintype "passive"))
    )
    (net (code "51") (name "Net-(J5-Pad4)") (class "Default")
      (node (ref "J5") (pin "4") (pinfunction "4_4") (pintype "passive"))
      (node (ref "J6") (pin "4") (pinfunction "4_4") (pintype "passive"))
    )
    (net (code "52") (name "Net-(J5-Pad5)") (class "Default")
      (node (ref "J5") (pin "5") (pinfunction "5_5") (pintype "passive"))
      (node (ref "J6") (pin "5") (pinfunction "5_5") (pintype "passive"))
    )
    (net (code "53") (name "Net-(J5-Pad6)") (class "Default")
      (node (ref "J5") (pin "6") (pinfunction "6_6") (pintype "passive"))
      (node (ref "J6") (pin "6") (pinfunction "6_6") (pintype "passive"))
    )
    (net (code "54") (name "Net-(J5-Pad7)") (class "Default")
      (node (ref "J5") (pin "7") (pinfunction "7_7") (pintype "passive"))
      (node (ref "J6") (pin "7") (pinfunction "7_7") (pintype "passive"))
    )
    (net (code "55") (name "Net-(J5-Pad8)") (class "Default")
      (node (ref "J5") (pin "8") (pinfunction "8_8") (pintype "passive"))
      (node (ref "J6") (pin "8") (pinfunction "8_8") (pintype "passive"))
    )
    (net (code "56") (name "Net-(J5-Pad9)") (class "Default")
      (node (ref "J5") (pin "9") (pinfunction "9_9") (pintype "passive"))
      (node (ref "J6") (pin "9") (pinfunction "9_9") (pintype "passive"))
    )
    (net (code "57") (name "Net-(J5-Pad10)") (class "Default")
      (node (ref "J5") (pin "10") (pinfunction "10_10") (pintype "passive"))
      (node (ref "J6") (pin "10") (pinfunction "10_10") (pintype "passive"))
    )
    (net (code "58") (name "Net-(J5-Pad11)") (class "Default")
      (node (ref "J5") (pin "11") (pinfunction "11_11") (pintype "passive"))
      (node (ref "J6") (pin "11") (pinfunction "11_11") (pintype "passive"))
    )
    (net (code "59") (name "Net-(J5-Pad12)") (class "Default")
      (node (ref "J5") (pin "12") (pinfunction "12_12") (pintype "passive"))
      (node (ref "J6") (pin "12") (pinfunction "12_12") (pintype "passive"))
    )
    (net (code "60") (name "Net-(J5-Pad13)") (class "Default")
      (node (ref "J5") (pin "13") (pinfunction "13_13") (pintype "passive"))
      (node (ref "J6") (pin "13") (pinfunction "13_13") (pintype "passive"))
    )
    (net (code "61") (name "Net-(J5-Pad14)") (class "Default")
      (node (ref "J5") (pin "14") (pinfunction "14_14") (pintype "passive"))
      (node (ref "J6") (pin "14") (pinfunction "14_14") (pintype "passive"))
    )
    (net (code "62") (name "Net-(J5-Pad15)") (class "Default")
      (node (ref "J5") (pin "15") (pinfunction "15_15") (pintype "passive"))
      (node (ref "J6") (pin "15") (pinfunction "15_15") (pintype "passive"))
    )
    (net (code "63") (name "Net-(J5-Pad16)") (class "Default")
      (node (ref "J5") (pin "16") (pinfunction "16_16") (pintype "passive"))
      (node (ref "J6") (pin "16") (pinfunction "16_16") (pintype "passive"))
    )
    (net (code "64") (name "Net-(J5-Pad17)") (class "Default")
      (node (ref "J5") (pin "17") (pinfunction "17_17") (pintype "passive"))
      (node (ref "J6") (pin "17") (pinfunction "17_17") (pintype "passive"))
    )
    (net (code "65") (name "Net-(J5-Pad18)") (class "Default")
      (node (ref "J5") (pin "18") (pinfunction "18_18") (pintype "passive"))
      (node (ref "J6") (pin "18") (pinfunction "18_18") (pintype "passive"))
    )
    (net (code "66") (name "Net-(J5-Pad19)") (class "Default")
      (node (ref "J5") (pin "19") (pinfunction "19_19") (pintype "passive"))
      (node (ref "J6") (pin "19") (pinfunction "19_19") (pintype "passive"))
    )
    (net (code "67") (name "Net-(J8-PadPIN)") (class "Default")
      (node (ref "J8") (pin "PIN") (pinfunction "PIN_PIN") (pintype "passive"))
      (node (ref "R11") (pin "1") (pinfunction "1_1") (pintype "passive"))
    )
    (net (code "68") (name "Net-(LED1-PadA)") (class "Default")
      (node (ref "LED1") (pin "A") (pinfunction "A_A") (pintype "passive"))
      (node (ref "R7") (pin "1") (pinfunction "1_1") (pintype "passive"))
    )
    (net (code "69") (name "Net-(LED2-PadA)") (class "Default")
      (node (ref "LED2") (pin "A") (pinfunction "A_A") (pintype "passive"))
      (node (ref "R6") (pin "1") (pinfunction "1_1") (pintype "passive"))
    )
    (net (code "70") (name "Net-(U1-MCLR)") (class "Default")
      (node (ref "ICP") (pin "1") (pinfunction "1_1") (pintype "passive"))
      (node (ref "R12") (pin "1") (pinfunction "1_1") (pintype "passive"))
      (node (ref "U1") (pin "7") (pinfunction "MCLR_7") (pintype "bidirectional"))
    )
    (net (code "71") (name "Net-(U1-RB0{slash}AN0{slash}CN2{slash}VR+{slash}PGD1{slash}PMA6)") (class "Default")
      (node (ref "LED2") (pin "C") (pinfunction "C_C") (pintype "passive"))
      (node (ref "U1") (pin "16") (pinfunction "RB0/AN0/CN2/VR+/PGD1/PMA6_16") (pintype "bidirectional"))
    )
    (net (code "72") (name "Net-(U1-RB1{slash}AN1{slash}CN3{slash}VR-{slash}PGC1)") (class "Default")
      (node (ref "LED1") (pin "C") (pinfunction "C_C") (pintype "passive"))
      (node (ref "U1") (pin "15") (pinfunction "RB1/AN1/CN3/VR-/PGC1_15") (pintype "bidirectional"))
    )
    (net (code "73") (name "Net-(U1-RB6{slash}AN6{slash}OCFA{slash}PGC2)") (class "Default")
      (node (ref "ICP") (pin "5") (pinfunction "5_5") (pintype "passive"))
      (node (ref "U1") (pin "17") (pinfunction "RB6/AN6/OCFA/PGC2_17") (pintype "bidirectional"))
    )
    (net (code "74") (name "Net-(U1-RB7{slash}AN7{slash}PGD2)") (class "Default")
      (node (ref "ICP") (pin "4") (pinfunction "4_4") (pintype "passive"))
      (node (ref "U1") (pin "18") (pinfunction "RB7/AN7/PGD2_18") (pintype "bidirectional"))
    )
    (net (code "75") (name "Net-(U1-RC12{slash}CLKI{slash}OSC1)") (class "Default")
      (node (ref "U1") (pin "39") (pinfunction "RC12/CLKI/OSC1_39") (pintype "bidirectional"))
      (node (ref "X1") (pin "3") (pinfunction "OUT_3") (pintype "output"))
    )
    (net (code "76") (name "Net-(U1-RD1{slash}OC2{slash}U1RTS{slash}BCLK1)") (class "Default")
      (node (ref "U1") (pin "49") (pinfunction "RD1/OC2/U1RTS/BCLK1_49") (pintype "bidirectional"))
      (node (ref "U2") (pin "1") (pinfunction "I0_1") (pintype "input"))
      (node (ref "U2") (pin "2") (pinfunction "I1_2") (pintype "input"))
    )
    (net (code "77") (name "Net-(U1-RF0)") (class "Default")
      (node (ref "U1") (pin "58") (pinfunction "RF0_58") (pintype "bidirectional"))
      (node (ref "U2") (pin "10") (pinfunction "I1_10") (pintype "input"))
      (node (ref "U2") (pin "9") (pinfunction "I0_9") (pintype "input"))
    )
    (net (code "78") (name "Net-(U1-VBUS)") (class "Default")
      (node (ref "R16") (pin "2") (pinfunction "2_2") (pintype "passive"))
      (node (ref "U1") (pin "34") (pinfunction "VBUS_34") (pintype "bidirectional"))
    )
    (net (code "79") (name "Net-(U1-VDDC)") (class "Default")
      (node (ref "C13") (pin "1") (pinfunction "1_1") (pintype "passive"))
      (node (ref "C14") (pin "1") (pinfunction "1_1") (pintype "passive"))
      (node (ref "U1") (pin "56") (pinfunction "VDDC_56") (pintype "bidirectional"))
    )
    (net (code "80") (name "Net-(U2A-O)") (class "Default")
      (node (ref "U2") (pin "3") (pinfunction "O_3") (pintype "output"))
      (node (ref "U2") (pin "4") (pinfunction "I0_4") (pintype "input"))
    )
    (net (code "81") (name "Net-(U2B-O)") (class "Default")
      (node (ref "U2") (pin "12") (pinfunction "I0_12") (pintype "input"))
      (node (ref "U2") (pin "13") (pinfunction "I1_13") (pintype "input"))
      (node (ref "U2") (pin "6") (pinfunction "O_6") (pintype "output"))
    )
    (net (code "82") (name "Net-(U3A-RESET)") (class "Default")
      (node (ref "C12") (pin "1") (pinfunction "1_1") (pintype "passive"))
      (node (ref "R1") (pin "2") (pinfunction "2_2") (pintype "passive"))
      (node (ref "U3A") (pin "6") (pinfunction "RESET_6") (pintype "input"))
      (node (ref "U3B") (pin "6") (pinfunction "RESET_6") (pintype "input"))
    )
    (net (code "83") (name "Net-(U3A-VID_IN)") (class "Default")
      (node (ref "C11") (pin "2") (pinfunction "2_2") (pintype "passive"))
      (node (ref "U3A") (pin "2") (pinfunction "VID_IN_2") (pintype "input"))
      (node (ref "U3B") (pin "2") (pinfunction "VID_IN_2") (pintype "input"))
    )
    (net (code "84") (name "Net-(U4A-+IN)") (class "Default")
      (node (ref "R15") (pin "1") (pinfunction "1_1") (pintype "passive"))
      (node (ref "U4") (pin "3") (pinfunction "+IN_3") (pintype "input"))
    )
    (net (code "85") (name "Net-(U4A--IN)") (class "Default")
      (node (ref "R13") (pin "2") (pinfunction "2_2") (pintype "passive"))
      (node (ref "R14") (pin "1") (pinfunction "1_1") (pintype "passive"))
      (node (ref "U4") (pin "4") (pinfunction "-IN_4") (pintype "input"))
    )
    (net (code "86") (name "Net-(U4A-OUT)") (class "Default")
      (node (ref "R10") (pin "2") (pinfunction "2_2") (pintype "passive"))
      (node (ref "R11") (pin "2") (pinfunction "2_2") (pintype "passive"))
      (node (ref "R13") (pin "1") (pinfunction "1_1") (pintype "passive"))
      (node (ref "U4") (pin "1") (pinfunction "OUT_1") (pintype "output"))
    )
    (net (code "87") (name "VDU_VIDEO") (class "Default")
      (node (ref "J1") (pin "7") (pinfunction "7_7") (pintype "passive"))
      (node (ref "J3") (pin "7") (pinfunction "7_7") (pintype "passive"))
      (node (ref "R10") (pin "1") (pinfunction "1_1") (pintype "passive"))
    )
    (net (code "88") (name "VIDEO") (class "Default")
      (node (ref "C11") (pin "1") (pinfunction "1_1") (pintype "passive"))
      (node (ref "J2") (pin "7") (pinfunction "7_7") (pintype "passive"))
      (node (ref "J4") (pin "7") (pinfunction "7_7") (pintype "passive"))
      (node (ref "R15") (pin "2") (pinfunction "2_2") (pintype "passive"))
      (node (ref "R17") (pin "1") (pinfunction "1_1") (pintype "passive"))
    )
    (net (code "89") (name "VIDEO_GND") (class "Default")
      (node (ref "C12") (pin "2") (pinfunction "2_2") (pintype "passive"))
      (node (ref "C15") (pin "2") (pinfunction "2_2") (pintype "passive"))
      (node (ref "C16") (pin "1") (pinfunction "1_1") (pintype "passive"))
      (node (ref "C5") (pin "2") (pinfunction "2_2") (pintype "passive"))
      (node (ref "FB1") (pin "1") (pinfunction "1_1") (pintype "passive"))
      (node (ref "J1") (pin "8") (pinfunction "8_8") (pintype "passive"))
      (node (ref "J2") (pin "8") (pinfunction "8_8") (pintype "passive"))
      (node (ref "J3") (pin "1") (pinfunction "1_1") (pintype "passive"))
      (node (ref "J3") (pin "10") (pinfunction "10_10") (pintype "passive"))
      (node (ref "J3") (pin "3") (pinfunction "3_3") (pintype "passive"))
      (node (ref "J3") (pin "6") (pinfunction "6_6") (pintype "passive"))
      (node (ref "J3") (pin "8") (pinfunction "8_8") (pintype "passive"))
      (node (ref "J3") (pin "9") (pinfunction "9_9") (pintype "passive"))
      (node (ref "J4") (pin "1") (pinfunction "1_1") (pintype "passive"))
      (node (ref "J4") (pin "10") (pinfunction "10_10") (pintype "passive"))
      (node (ref "J4") (pin "3") (pinfunction "3_3") (pintype "passive"))
      (node (ref "J4") (pin "6") (pinfunction "6_6") (pintype "passive"))
      (node (ref "J4") (pin "8") (pinfunction "8_8") (pintype "passive"))
      (node (ref "J4") (pin "9") (pinfunction "9_9") (pintype "passive"))
      (node (ref "J8") (pin "SHLD") (pinfunction "SHLD_SHLD") (pintype "passive"))
      (node (ref "R1") (pin "1") (pinfunction "1_1") (pintype "passive"))
      (node (ref "R14") (pin "2") (pinfunction "2_2") (pintype "passive"))
      (node (ref "R17") (pin "2") (pinfunction "2_2") (pintype "passive"))
      (node (ref "R3") (pin "1") (pinfunction "1_1") (pintype "passive"))
      (node (ref "R5") (pin "1") (pinfunction "1_1") (pintype "passive"))
      (node (ref "U3A") (pin "4") (pinfunction "GND_4") (pintype "power_in"))
      (node (ref "U3B") (pin "4") (pinfunction "GND_4") (pintype "power_in"))
      (node (ref "U4") (pin "2") (pinfunction "GND_2") (pintype "power_in"))
    )
    (net (code "90") (name "VSYNC") (class "Default")
      (node (ref "U1") (pin "44") (pinfunction "RD10/IC3/INT3/PMCS2/SCL1_44") (pintype "bidirectional"))
      (node (ref "U3A") (pin "3") (pinfunction "VSYNC_3") (pintype "output"))
      (node (ref "U3B") (pin "3") (pinfunction "VSYNC_3") (pintype "output"))
    )
    (net (code "91") (name "unconnected-(J1-Pad1)") (class "Default")
      (node (ref "J1") (pin "1") (pinfunction "1_1") (pintype "passive"))
    )
    (net (code "92") (name "unconnected-(J1-Pad2)") (class "Default")
      (node (ref "J1") (pin "2") (pinfunction "2_2") (pintype "passive"))
    )
    (net (code "93") (name "unconnected-(J1-Pad3)") (class "Default")
      (node (ref "J1") (pin "3") (pinfunction "3_3") (pintype "passive"))
    )
    (net (code "94") (name "unconnected-(J1-Pad4)") (class "Default")
      (node (ref "J1") (pin "4") (pinfunction "4_4") (pintype "passive"))
    )
    (net (code "95") (name "unconnected-(J1-Pad5)") (class "Default")
      (node (ref "J1") (pin "5") (pinfunction "5_5") (pintype "passive"))
    )
    (net (code "96") (name "unconnected-(J1-Pad6)") (class "Default")
      (node (ref "J1") (pin "6") (pinfunction "6_6") (pintype "passive"))
    )
    (net (code "97") (name "unconnected-(J1-Pad9)") (class "Default")
      (node (ref "J1") (pin "9") (pinfunction "9_9") (pintype "passive"))
    )
    (net (code "98") (name "unconnected-(J1-Pad10)") (class "Default")
      (node (ref "J1") (pin "10") (pinfunction "10_10") (pintype "passive"))
    )
    (net (code "99") (name "unconnected-(J2-Pad1)") (class "Default")
      (node (ref "J2") (pin "1") (pinfunction "1_1") (pintype "passive"))
    )
    (net (code "100") (name "unconnected-(J2-Pad2)") (class "Default")
      (node (ref "J2") (pin "2") (pinfunction "2_2") (pintype "passive"))
    )
    (net (code "101") (name "unconnected-(J2-Pad3)") (class "Default")
      (node (ref "J2") (pin "3") (pinfunction "3_3") (pintype "passive"))
    )
    (net (code "102") (name "unconnected-(J2-Pad4)") (class "Default")
      (node (ref "J2") (pin "4") (pinfunction "4_4") (pintype "passive"))
    )
    (net (code "103") (name "unconnected-(J2-Pad5)") (class "Default")
      (node (ref "J2") (pin "5") (pinfunction "5_5") (pintype "passive"))
    )
    (net (code "104") (name "unconnected-(J2-Pad6)") (class "Default")
      (node (ref "J2") (pin "6") (pinfunction "6_6") (pintype "passive"))
    )
    (net (code "105") (name "unconnected-(J2-Pad9)") (class "Default")
      (node (ref "J2") (pin "9") (pinfunction "9_9") (pintype "passive"))
    )
    (net (code "106") (name "unconnected-(J2-Pad10)") (class "Default")
      (node (ref "J2") (pin "10") (pinfunction "10_10") (pintype "passive"))
    )
    (net (code "107") (name "unconnected-(U1-USBID{slash}RF3-Pad33)") (class "Default")
      (node (ref "U1") (pin "33") (pinfunction "USBID/RF3_33") (pintype "bidirectional"))
    )
    (net (code "108") (name "unconnected-(U3A-BURST-Pad5)") (class "Default")
      (node (ref "U3A") (pin "5") (pinfunction "BURST_5") (pintype "output"))
    )
    (net (code "109") (name "unconnected-(U3A-ODD{slash}EVEN-Pad7)") (class "Default")
      (node (ref "U3A") (pin "7") (pinfunction "ODD/EVEN_7") (pintype "output"))
    )
    (net (code "110") (name "unconnected-(U3B-BURST-Pad5)") (class "Default")
      (node (ref "U3B") (pin "5") (pinfunction "BURST_5") (pintype "output"))
    )
    (net (code "111") (name "unconnected-(U3B-ODD{slash}EVEN-Pad7)") (class "Default")
      (node (ref "U3B") (pin "7") (pinfunction "ODD/EVEN_7") (pintype "output"))
    )
    (net (code "112") (name "{slash}MOUSE_VBUS_EN") (class "Default")
      (node (ref "U1") (pin "11") (pinfunction "RB5/AN5/CN7/C1IN+/VBUSON_11") (pintype "bidirectional"))
      (node (ref "U5B") (pin "4") (pinfunction "/EN_4") (pintype "input"))
    )
    (net (code "113") (name "{slash}MOUSE_VBUS_OC") (class "Default")
      (node (ref "R9") (pin "2") (pinfunction "2_2") (pintype "passive"))
      (node (ref "U1") (pin "12") (pinfunction "RB4/AN4/CN6/C1IN-_12") (pintype "bidirectional"))
      (node (ref "U5B") (pin "3") (pinfunction "/OC_3") (pintype "output"))
    )
  )
)
